# A607B.net
KiCad netlist of a schematic drawn in EAGLE
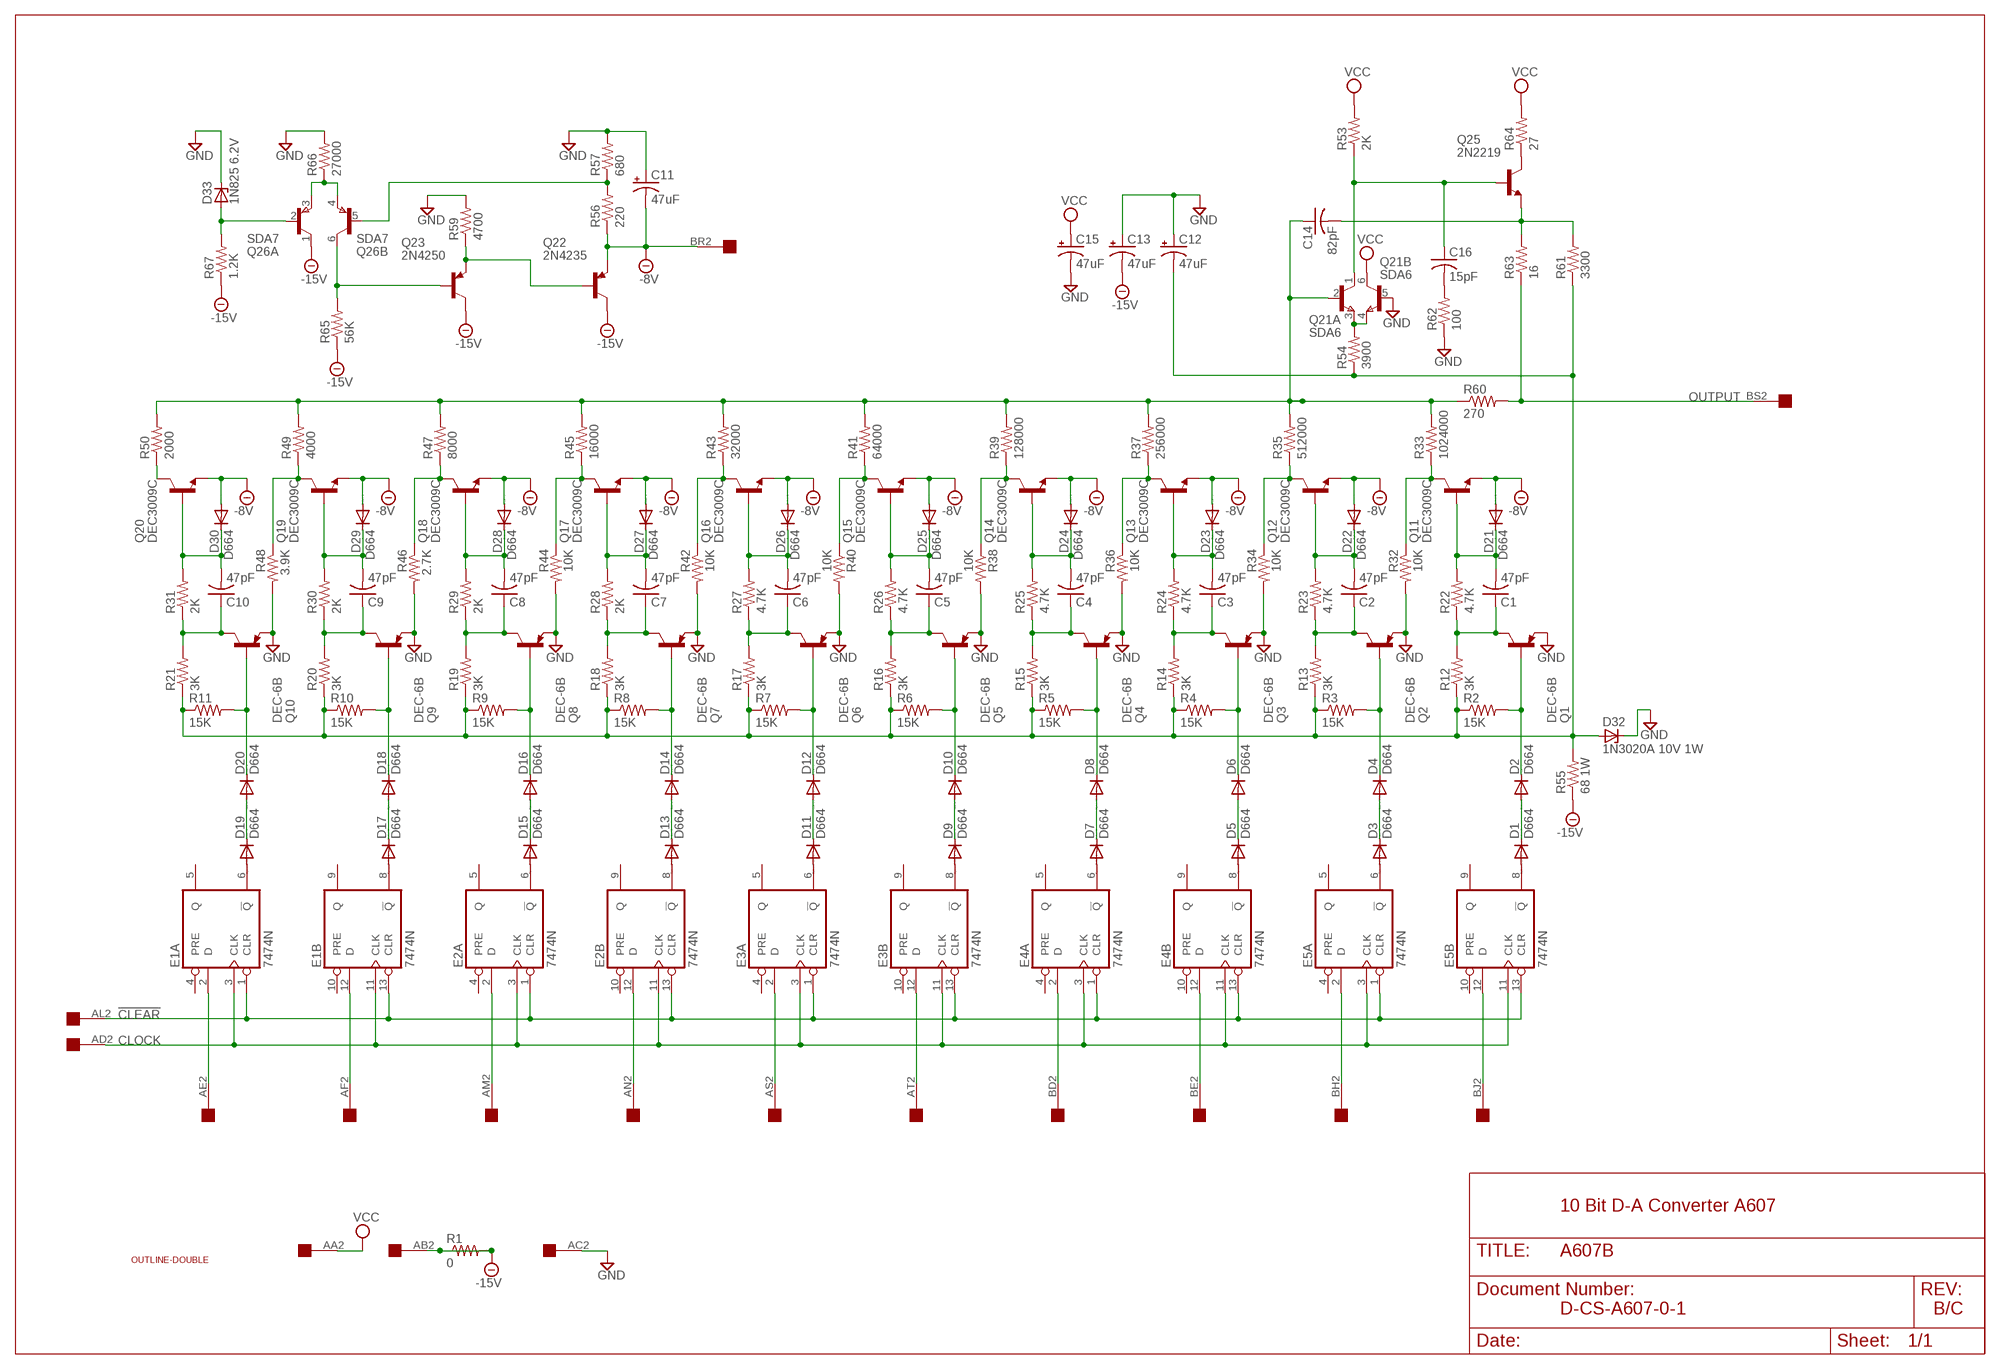
[diagram p0: schematic, sheet 1]

(export (version "E")
  (design (tool "Eeschema 10.0.6"))
  (components
    (comp (ref "C1")
      (value "47pF")
      (footprint "eagle-import:C075-032X103")
      (libsource (lib "eagle-import") (part "C-US075-032X103"))
    )
    (comp (ref "C2")
      (value "47pF")
      (footprint "eagle-import:C075-032X103")
      (libsource (lib "eagle-import") (part "C-US075-032X103"))
    )
    (comp (ref "C3")
      (value "47pF")
      (footprint "eagle-import:C075-032X103")
      (libsource (lib "eagle-import") (part "C-US075-032X103"))
    )
    (comp (ref "C4")
      (value "47pF")
      (footprint "eagle-import:C075-032X103")
      (libsource (lib "eagle-import") (part "C-US075-032X103"))
    )
    (comp (ref "C5")
      (value "47pF")
      (footprint "eagle-import:C075-032X103")
      (libsource (lib "eagle-import") (part "C-US075-032X103"))
    )
    (comp (ref "C6")
      (value "47pF")
      (footprint "eagle-import:C075-032X103")
      (libsource (lib "eagle-import") (part "C-US075-032X103"))
    )
    (comp (ref "C7")
      (value "47pF")
      (footprint "eagle-import:C075-032X103")
      (libsource (lib "eagle-import") (part "C-US075-032X103"))
    )
    (comp (ref "C8")
      (value "47pF")
      (footprint "eagle-import:C075-032X103")
      (libsource (lib "eagle-import") (part "C-US075-032X103"))
    )
    (comp (ref "C9")
      (value "47pF")
      (footprint "eagle-import:C075-032X103")
      (libsource (lib "eagle-import") (part "C-US075-032X103"))
    )
    (comp (ref "C10")
      (value "47pF")
      (footprint "eagle-import:C075-032X103")
      (libsource (lib "eagle-import") (part "C-US075-032X103"))
    )
    (comp (ref "C11")
      (value "47uF")
      (footprint "eagle-import:E25-9")
      (libsource (lib "eagle-import") (part "CPOL-USE25-9AXIAL"))
    )
    (comp (ref "C12")
      (value "47uF")
      (footprint "eagle-import:E25-9")
      (libsource (lib "eagle-import") (part "CPOL-USE25-9AXIAL"))
    )
    (comp (ref "C13")
      (value "47uF")
      (footprint "eagle-import:E25-9")
      (libsource (lib "eagle-import") (part "CPOL-USE25-9AXIAL"))
    )
    (comp (ref "C14")
      (value "82pF")
      (footprint "eagle-import:C050-025X075")
      (libsource (lib "eagle-import") (part "C-US050-025X075"))
    )
    (comp (ref "C15")
      (value "47uF")
      (footprint "eagle-import:E25-9")
      (libsource (lib "eagle-import") (part "CPOL-USE25-9AXIAL"))
    )
    (comp (ref "C16")
      (value "15pF")
      (footprint "eagle-import:C050-025X075")
      (libsource (lib "eagle-import") (part "C-US050-025X075"))
    )
    (comp (ref "D1")
      (value "D664")
      (footprint "eagle-import:DO35-10")
      (libsource (lib "eagle-import") (part "DIODE-DO35-10"))
    )
    (comp (ref "D2")
      (value "D664")
      (footprint "eagle-import:DO35-10")
      (libsource (lib "eagle-import") (part "DIODE-DO35-10"))
    )
    (comp (ref "D3")
      (value "D664")
      (footprint "eagle-import:DO35-10")
      (libsource (lib "eagle-import") (part "DIODE-DO35-10"))
    )
    (comp (ref "D4")
      (value "D664")
      (footprint "eagle-import:DO35-10")
      (libsource (lib "eagle-import") (part "DIODE-DO35-10"))
    )
    (comp (ref "D5")
      (value "D664")
      (footprint "eagle-import:DO35-10")
      (libsource (lib "eagle-import") (part "DIODE-DO35-10"))
    )
    (comp (ref "D6")
      (value "D664")
      (footprint "eagle-import:DO35-10")
      (libsource (lib "eagle-import") (part "DIODE-DO35-10"))
    )
    (comp (ref "D7")
      (value "D664")
      (footprint "eagle-import:DO35-10")
      (libsource (lib "eagle-import") (part "DIODE-DO35-10"))
    )
    (comp (ref "D8")
      (value "D664")
      (footprint "eagle-import:DO35-10")
      (libsource (lib "eagle-import") (part "DIODE-DO35-10"))
    )
    (comp (ref "D9")
      (value "D664")
      (footprint "eagle-import:DO35-10")
      (libsource (lib "eagle-import") (part "DIODE-DO35-10"))
    )
    (comp (ref "D10")
      (value "D664")
      (footprint "eagle-import:DO35-10")
      (libsource (lib "eagle-import") (part "DIODE-DO35-10"))
    )
    (comp (ref "D11")
      (value "D664")
      (footprint "eagle-import:DO35-10")
      (libsource (lib "eagle-import") (part "DIODE-DO35-10"))
    )
    (comp (ref "D12")
      (value "D664")
      (footprint "eagle-import:DO35-10")
      (libsource (lib "eagle-import") (part "DIODE-DO35-10"))
    )
    (comp (ref "D13")
      (value "D664")
      (footprint "eagle-import:DO35-10")
      (libsource (lib "eagle-import") (part "DIODE-DO35-10"))
    )
    (comp (ref "D14")
      (value "D664")
      (footprint "eagle-import:DO35-10")
      (libsource (lib "eagle-import") (part "DIODE-DO35-10"))
    )
    (comp (ref "D15")
      (value "D664")
      (footprint "eagle-import:DO35-10")
      (libsource (lib "eagle-import") (part "DIODE-DO35-10"))
    )
    (comp (ref "D16")
      (value "D664")
      (footprint "eagle-import:DO35-10")
      (libsource (lib "eagle-import") (part "DIODE-DO35-10"))
    )
    (comp (ref "D17")
      (value "D664")
      (footprint "eagle-import:DO35-10")
      (libsource (lib "eagle-import") (part "DIODE-DO35-10"))
    )
    (comp (ref "D18")
      (value "D664")
      (footprint "eagle-import:DO35-10")
      (libsource (lib "eagle-import") (part "DIODE-DO35-10"))
    )
    (comp (ref "D19")
      (value "D664")
      (footprint "eagle-import:DO35-10")
      (libsource (lib "eagle-import") (part "DIODE-DO35-10"))
    )
    (comp (ref "D20")
      (value "D664")
      (footprint "eagle-import:DO35-10")
      (libsource (lib "eagle-import") (part "DIODE-DO35-10"))
    )
    (comp (ref "D21")
      (value "D664")
      (footprint "eagle-import:DO35-10")
      (libsource (lib "eagle-import") (part "DIODE-DO35-10"))
    )
    (comp (ref "D22")
      (value "D664")
      (footprint "eagle-import:DO35-10")
      (libsource (lib "eagle-import") (part "DIODE-DO35-10"))
    )
    (comp (ref "D23")
      (value "D664")
      (footprint "eagle-import:DO35-10")
      (libsource (lib "eagle-import") (part "DIODE-DO35-10"))
    )
    (comp (ref "D24")
      (value "D664")
      (footprint "eagle-import:DO35-10")
      (libsource (lib "eagle-import") (part "DIODE-DO35-10"))
    )
    (comp (ref "D25")
      (value "D664")
      (footprint "eagle-import:DO35-10")
      (libsource (lib "eagle-import") (part "DIODE-DO35-10"))
    )
    (comp (ref "D26")
      (value "D664")
      (footprint "eagle-import:DO35-10")
      (libsource (lib "eagle-import") (part "DIODE-DO35-10"))
    )
    (comp (ref "D27")
      (value "D664")
      (footprint "eagle-import:DO35-10")
      (libsource (lib "eagle-import") (part "DIODE-DO35-10"))
    )
    (comp (ref "D28")
      (value "D664")
      (footprint "eagle-import:DO35-10")
      (libsource (lib "eagle-import") (part "DIODE-DO35-10"))
    )
    (comp (ref "D29")
      (value "D664")
      (footprint "eagle-import:DO35-10")
      (libsource (lib "eagle-import") (part "DIODE-DO35-10"))
    )
    (comp (ref "D30")
      (value "D664")
      (footprint "eagle-import:DO35-10")
      (libsource (lib "eagle-import") (part "DIODE-DO35-10"))
    )
    (comp (ref "D32")
      (value "1N3020A 10V 1W")
      (footprint "eagle-import:DO13M")
      (libsource (lib "eagle-import") (part "ZENER-DIODEDO13M"))
    )
    (comp (ref "D33")
      (value "1N825 6.2V")
      (footprint "eagle-import:DO35Z10")
      (libsource (lib "eagle-import") (part "ZENER-DIODEDO35Z10"))
    )
    (comp (ref "E1")
      (value "7474N")
      (footprint "eagle-import:DIL14")
      (libsource (lib "eagle-import") (part "7474NS"))
    )
    (comp (ref "E2")
      (value "7474N")
      (footprint "eagle-import:DIL14")
      (libsource (lib "eagle-import") (part "7474NS"))
    )
    (comp (ref "E3")
      (value "7474N")
      (footprint "eagle-import:DIL14")
      (libsource (lib "eagle-import") (part "7474NS"))
    )
    (comp (ref "E4")
      (value "7474N")
      (footprint "eagle-import:DIL14")
      (libsource (lib "eagle-import") (part "7474NS"))
    )
    (comp (ref "E5")
      (value "7474N")
      (footprint "eagle-import:DIL14")
      (libsource (lib "eagle-import") (part "7474NS"))
    )
    (comp (ref "Q1")
      (value "DEC-6B")
      (footprint "eagle-import:TO5")
      (libsource (lib "eagle-import") (part "-PNP-TO5"))
    )
    (comp (ref "Q2")
      (value "DEC-6B")
      (footprint "eagle-import:TO5")
      (libsource (lib "eagle-import") (part "-PNP-TO5"))
    )
    (comp (ref "Q3")
      (value "DEC-6B")
      (footprint "eagle-import:TO5")
      (libsource (lib "eagle-import") (part "-PNP-TO5"))
    )
    (comp (ref "Q4")
      (value "DEC-6B")
      (footprint "eagle-import:TO5")
      (libsource (lib "eagle-import") (part "-PNP-TO5"))
    )
    (comp (ref "Q5")
      (value "DEC-6B")
      (footprint "eagle-import:TO5")
      (libsource (lib "eagle-import") (part "-PNP-TO5"))
    )
    (comp (ref "Q6")
      (value "DEC-6B")
      (footprint "eagle-import:TO5")
      (libsource (lib "eagle-import") (part "-PNP-TO5"))
    )
    (comp (ref "Q7")
      (value "DEC-6B")
      (footprint "eagle-import:TO5")
      (libsource (lib "eagle-import") (part "-PNP-TO5"))
    )
    (comp (ref "Q8")
      (value "DEC-6B")
      (footprint "eagle-import:TO5")
      (libsource (lib "eagle-import") (part "-PNP-TO5"))
    )
    (comp (ref "Q9")
      (value "DEC-6B")
      (footprint "eagle-import:TO5")
      (libsource (lib "eagle-import") (part "-PNP-TO5"))
    )
    (comp (ref "Q10")
      (value "DEC-6B")
      (footprint "eagle-import:TO5")
      (libsource (lib "eagle-import") (part "-PNP-TO5"))
    )
    (comp (ref "Q11")
      (value "DEC3009C")
      (footprint "eagle-import:TO5")
      (libsource (lib "eagle-import") (part "-NPN-TO5"))
    )
    (comp (ref "Q12")
      (value "DEC3009C")
      (footprint "eagle-import:TO5")
      (libsource (lib "eagle-import") (part "-NPN-TO5"))
    )
    (comp (ref "Q13")
      (value "DEC3009C")
      (footprint "eagle-import:TO5")
      (libsource (lib "eagle-import") (part "-NPN-TO5"))
    )
    (comp (ref "Q14")
      (value "DEC3009C")
      (footprint "eagle-import:TO5")
      (libsource (lib "eagle-import") (part "-NPN-TO5"))
    )
    (comp (ref "Q15")
      (value "DEC3009C")
      (footprint "eagle-import:TO5")
      (libsource (lib "eagle-import") (part "-NPN-TO5"))
    )
    (comp (ref "Q16")
      (value "DEC3009C")
      (footprint "eagle-import:TO5")
      (libsource (lib "eagle-import") (part "-NPN-TO5"))
    )
    (comp (ref "Q17")
      (value "DEC3009C")
      (footprint "eagle-import:TO5")
      (libsource (lib "eagle-import") (part "-NPN-TO5"))
    )
    (comp (ref "Q18")
      (value "DEC3009C")
      (footprint "eagle-import:TO5")
      (libsource (lib "eagle-import") (part "-NPN-TO5"))
    )
    (comp (ref "Q19")
      (value "DEC3009C")
      (footprint "eagle-import:TO5")
      (libsource (lib "eagle-import") (part "-NPN-TO5"))
    )
    (comp (ref "Q20")
      (value "DEC3009C")
      (footprint "eagle-import:TO5")
      (libsource (lib "eagle-import") (part "-NPN-TO5"))
    )
    (comp (ref "Q21")
      (value "SDA6")
      (footprint "eagle-import:TO78")
      (libsource (lib "eagle-import") (part "MAT-02H"))
    )
    (comp (ref "Q22")
      (value "2N4235")
      (footprint "eagle-import:TO5")
      (libsource (lib "eagle-import") (part "-PNP-TO5"))
    )
    (comp (ref "Q23")
      (value "2N4250")
      (footprint "eagle-import:TO5")
      (libsource (lib "eagle-import") (part "-PNP-TO5"))
    )
    (comp (ref "Q25")
      (value "2N2219")
      (footprint "eagle-import:TO5")
      (libsource (lib "eagle-import") (part "-NPN-TO5"))
    )
    (comp (ref "Q26")
      (value "SDA7")
      (footprint "eagle-import:TO78")
      (libsource (lib "eagle-import") (part "MAT-03H"))
    )
    (comp (ref "R1")
      (value "0")
      (footprint "eagle-import:0818_25")
      (libsource (lib "eagle-import") (part "R-US_0818/25"))
    )
    (comp (ref "R2")
      (value "15K")
      (footprint "eagle-import:0207_10")
      (libsource (lib "eagle-import") (part "R-US_0207/10"))
    )
    (comp (ref "R3")
      (value "15K")
      (footprint "eagle-import:0207_10")
      (libsource (lib "eagle-import") (part "R-US_0207/10"))
    )
    (comp (ref "R4")
      (value "15K")
      (footprint "eagle-import:0207_10")
      (libsource (lib "eagle-import") (part "R-US_0207/10"))
    )
    (comp (ref "R5")
      (value "15K")
      (footprint "eagle-import:0207_10")
      (libsource (lib "eagle-import") (part "R-US_0207/10"))
    )
    (comp (ref "R6")
      (value "15K")
      (footprint "eagle-import:0207_10")
      (libsource (lib "eagle-import") (part "R-US_0207/10"))
    )
    (comp (ref "R7")
      (value "15K")
      (footprint "eagle-import:0207_10")
      (libsource (lib "eagle-import") (part "R-US_0207/10"))
    )
    (comp (ref "R8")
      (value "15K")
      (footprint "eagle-import:0207_10")
      (libsource (lib "eagle-import") (part "R-US_0207/10"))
    )
    (comp (ref "R9")
      (value "15K")
      (footprint "eagle-import:0207_10")
      (libsource (lib "eagle-import") (part "R-US_0207/10"))
    )
    (comp (ref "R10")
      (value "15K")
      (footprint "eagle-import:0207_10")
      (libsource (lib "eagle-import") (part "R-US_0207/10"))
    )
    (comp (ref "R11")
      (value "15K")
      (footprint "eagle-import:0207_10")
      (libsource (lib "eagle-import") (part "R-US_0207/10"))
    )
    (comp (ref "R12")
      (value "3K")
      (footprint "eagle-import:0207_10")
      (libsource (lib "eagle-import") (part "R-US_0207/10"))
    )
    (comp (ref "R13")
      (value "3K")
      (footprint "eagle-import:0207_10")
      (libsource (lib "eagle-import") (part "R-US_0207/10"))
    )
    (comp (ref "R14")
      (value "3K")
      (footprint "eagle-import:0207_10")
      (libsource (lib "eagle-import") (part "R-US_0207/10"))
    )
    (comp (ref "R15")
      (value "3K")
      (footprint "eagle-import:0207_10")
      (libsource (lib "eagle-import") (part "R-US_0207/10"))
    )
    (comp (ref "R16")
      (value "3K")
      (footprint "eagle-import:0207_10")
      (libsource (lib "eagle-import") (part "R-US_0207/10"))
    )
    (comp (ref "R17")
      (value "3K")
      (footprint "eagle-import:0207_10")
      (libsource (lib "eagle-import") (part "R-US_0207/10"))
    )
    (comp (ref "R18")
      (value "3K")
      (footprint "eagle-import:0207_10")
      (libsource (lib "eagle-import") (part "R-US_0207/10"))
    )
    (comp (ref "R19")
      (value "3K")
      (footprint "eagle-import:0207_10")
      (libsource (lib "eagle-import") (part "R-US_0207/10"))
    )
    (comp (ref "R20")
      (value "3K")
      (footprint "eagle-import:0207_10")
      (libsource (lib "eagle-import") (part "R-US_0207/10"))
    )
    (comp (ref "R21")
      (value "3K")
      (footprint "eagle-import:0207_10")
      (libsource (lib "eagle-import") (part "R-US_0207/10"))
    )
    (comp (ref "R22")
      (value "4.7K")
      (footprint "eagle-import:0207_10")
      (libsource (lib "eagle-import") (part "R-US_0207/10"))
    )
    (comp (ref "R23")
      (value "4.7K")
      (footprint "eagle-import:0207_10")
      (libsource (lib "eagle-import") (part "R-US_0207/10"))
    )
    (comp (ref "R24")
      (value "4.7K")
      (footprint "eagle-import:0207_10")
      (libsource (lib "eagle-import") (part "R-US_0207/10"))
    )
    (comp (ref "R25")
      (value "4.7K")
      (footprint "eagle-import:0207_10")
      (libsource (lib "eagle-import") (part "R-US_0207/10"))
    )
    (comp (ref "R26")
      (value "4.7K")
      (footprint "eagle-import:0207_10")
      (libsource (lib "eagle-import") (part "R-US_0207/10"))
    )
    (comp (ref "R27")
      (value "4.7K")
      (footprint "eagle-import:0207_10")
      (libsource (lib "eagle-import") (part "R-US_0207/10"))
    )
    (comp (ref "R28")
      (value "2K")
      (footprint "eagle-import:0207_10")
      (libsource (lib "eagle-import") (part "R-US_0207/10"))
    )
    (comp (ref "R29")
      (value "2K")
      (footprint "eagle-import:0207_10")
      (libsource (lib "eagle-import") (part "R-US_0207/10"))
    )
    (comp (ref "R30")
      (value "2K")
      (footprint "eagle-import:0207_10")
      (libsource (lib "eagle-import") (part "R-US_0207/10"))
    )
    (comp (ref "R31")
      (value "2K")
      (footprint "eagle-import:0207_10")
      (libsource (lib "eagle-import") (part "R-US_0207/10"))
    )
    (comp (ref "R32")
      (value "10K")
      (footprint "eagle-import:0207_10")
      (libsource (lib "eagle-import") (part "R-US_0207/10"))
    )
    (comp (ref "R33")
      (value "1024000")
      (footprint "eagle-import:0414_20")
      (libsource (lib "eagle-import") (part "R-US_0414/20"))
    )
    (comp (ref "R34")
      (value "10K")
      (footprint "eagle-import:0207_10")
      (libsource (lib "eagle-import") (part "R-US_0207/10"))
    )
    (comp (ref "R35")
      (value "512000")
      (footprint "eagle-import:0414_20")
      (libsource (lib "eagle-import") (part "R-US_0414/20"))
    )
    (comp (ref "R36")
      (value "10K")
      (footprint "eagle-import:0207_10")
      (libsource (lib "eagle-import") (part "R-US_0207/10"))
    )
    (comp (ref "R37")
      (value "256000")
      (footprint "eagle-import:0207_15")
      (libsource (lib "eagle-import") (part "R-US_0207/15"))
    )
    (comp (ref "R38")
      (value "10K")
      (footprint "eagle-import:0207_10")
      (libsource (lib "eagle-import") (part "R-US_0207/10"))
    )
    (comp (ref "R39")
      (value "128000")
      (footprint "eagle-import:0207_15")
      (libsource (lib "eagle-import") (part "R-US_0207/15"))
    )
    (comp (ref "R40")
      (value "10K")
      (footprint "eagle-import:0207_10")
      (libsource (lib "eagle-import") (part "R-US_0207/10"))
    )
    (comp (ref "R41")
      (value "64000")
      (footprint "eagle-import:0207_15")
      (libsource (lib "eagle-import") (part "R-US_0207/15"))
    )
    (comp (ref "R42")
      (value "10K")
      (footprint "eagle-import:0207_10")
      (libsource (lib "eagle-import") (part "R-US_0207/10"))
    )
    (comp (ref "R43")
      (value "32000")
      (footprint "eagle-import:0207_15")
      (libsource (lib "eagle-import") (part "R-US_0207/15"))
    )
    (comp (ref "R44")
      (value "10K")
      (footprint "eagle-import:0207_10")
      (libsource (lib "eagle-import") (part "R-US_0207/10"))
    )
    (comp (ref "R45")
      (value "16000")
      (footprint "eagle-import:0207_15")
      (libsource (lib "eagle-import") (part "R-US_0207/15"))
    )
    (comp (ref "R46")
      (value "2.7K")
      (footprint "eagle-import:0207_10")
      (libsource (lib "eagle-import") (part "R-US_0207/10"))
    )
    (comp (ref "R47")
      (value "8000")
      (footprint "eagle-import:0207_15")
      (libsource (lib "eagle-import") (part "R-US_0207/15"))
    )
    (comp (ref "R48")
      (value "3.9K")
      (footprint "eagle-import:0207_10")
      (libsource (lib "eagle-import") (part "R-US_0207/10"))
    )
    (comp (ref "R49")
      (value "4000")
      (footprint "eagle-import:0207_15")
      (libsource (lib "eagle-import") (part "R-US_0207/15"))
    )
    (comp (ref "R50")
      (value "2000")
      (footprint "eagle-import:0207_15")
      (libsource (lib "eagle-import") (part "R-US_0207/15"))
    )
    (comp (ref "R53")
      (value "2K")
      (footprint "eagle-import:0207_10")
      (libsource (lib "eagle-import") (part "R-US_0207/10"))
    )
    (comp (ref "R54")
      (value "3900")
      (footprint "eagle-import:0207_10")
      (libsource (lib "eagle-import") (part "R-US_0207/10"))
    )
    (comp (ref "R55")
      (value "68 1W")
      (footprint "eagle-import:0818_25")
      (libsource (lib "eagle-import") (part "R-US_0818/25"))
    )
    (comp (ref "R56")
      (value "220")
      (footprint "eagle-import:0207_10")
      (libsource (lib "eagle-import") (part "R-US_0207/10"))
    )
    (comp (ref "R57")
      (value "680")
      (footprint "eagle-import:0207_10")
      (libsource (lib "eagle-import") (part "R-US_0207/10"))
    )
    (comp (ref "R59")
      (value "4700")
      (footprint "eagle-import:0207_10")
      (libsource (lib "eagle-import") (part "R-US_0207/10"))
    )
    (comp (ref "R60")
      (value "270")
      (footprint "eagle-import:0207_10")
      (libsource (lib "eagle-import") (part "R-US_0207/10"))
    )
    (comp (ref "R61")
      (value "3300")
      (footprint "eagle-import:0207_10")
      (libsource (lib "eagle-import") (part "R-US_0207/10"))
    )
    (comp (ref "R62")
      (value "100")
      (footprint "eagle-import:0207_10")
      (libsource (lib "eagle-import") (part "R-US_0207/10"))
    )
    (comp (ref "R63")
      (value "16")
      (footprint "eagle-import:0207_10")
      (libsource (lib "eagle-import") (part "R-US_0207/10"))
    )
    (comp (ref "R64")
      (value "27")
      (footprint "eagle-import:0207_10")
      (libsource (lib "eagle-import") (part "R-US_0207/10"))
    )
    (comp (ref "R65")
      (value "56K")
      (footprint "eagle-import:0207_10")
      (libsource (lib "eagle-import") (part "R-US_0207/10"))
    )
    (comp (ref "R66")
      (value "27000")
      (footprint "eagle-import:0207_10")
      (libsource (lib "eagle-import") (part "R-US_0207/10"))
    )
    (comp (ref "R67")
      (value "1.2K")
      (footprint "eagle-import:0207_10")
      (libsource (lib "eagle-import") (part "R-US_0207/10"))
    )
    (comp (ref "U$1")
      (value "OUTLINE-DOUBLE")
      (footprint "eagle-import:DOUBLE")
      (libsource (lib "eagle-import") (part "OUTLINE-DOUBLE"))
    )
    (comp (ref "U$2")
      (value "DOUBLE")
      (footprint "eagle-import:EDGE-CON4")
      (libsource (lib "eagle-import") (part "DOUBLE"))
    )
  )
  (nets
    (net (code "1") (name "-8V") (class "Default")
      (node (ref "C11") (pin "-") (pinfunction "-_-") (pintype "passive"))
      (node (ref "D21") (pin "A") (pinfunction "A_A") (pintype "passive"))
      (node (ref "D22") (pin "A") (pinfunction "A_A") (pintype "passive"))
      (node (ref "D23") (pin "A") (pinfunction "A_A") (pintype "passive"))
      (node (ref "D24") (pin "A") (pinfunction "A_A") (pintype "passive"))
      (node (ref "D25") (pin "A") (pinfunction "A_A") (pintype "passive"))
      (node (ref "D26") (pin "A") (pinfunction "A_A") (pintype "passive"))
      (node (ref "D27") (pin "A") (pinfunction "A_A") (pintype "passive"))
      (node (ref "D28") (pin "A") (pinfunction "A_A") (pintype "passive"))
      (node (ref "D29") (pin "A") (pinfunction "A_A") (pintype "passive"))
      (node (ref "D30") (pin "A") (pinfunction "A_A") (pintype "passive"))
      (node (ref "Q11") (pin "1") (pinfunction "E_1") (pintype "passive"))
      (node (ref "Q12") (pin "1") (pinfunction "E_1") (pintype "passive"))
      (node (ref "Q13") (pin "1") (pinfunction "E_1") (pintype "passive"))
      (node (ref "Q14") (pin "1") (pinfunction "E_1") (pintype "passive"))
      (node (ref "Q15") (pin "1") (pinfunction "E_1") (pintype "passive"))
      (node (ref "Q16") (pin "1") (pinfunction "E_1") (pintype "passive"))
      (node (ref "Q17") (pin "1") (pinfunction "E_1") (pintype "passive"))
      (node (ref "Q18") (pin "1") (pinfunction "E_1") (pintype "passive"))
      (node (ref "Q19") (pin "1") (pinfunction "E_1") (pintype "passive"))
      (node (ref "Q20") (pin "1") (pinfunction "E_1") (pintype "passive"))
      (node (ref "Q22") (pin "1") (pinfunction "E_1") (pintype "passive"))
      (node (ref "R56") (pin "1") (pinfunction "1_1") (pintype "passive"))
      (node (ref "U$2") (pin "BR2") (pinfunction "1_BR2") (pintype "bidirectional"))
    )
    (net (code "2") (name "-15V") (class "Default")
      (node (ref "C13") (pin "-") (pinfunction "-_-") (pintype "passive"))
      (node (ref "Q22") (pin "3") (pinfunction "C_3") (pintype "passive"))
      (node (ref "Q23") (pin "3") (pinfunction "C_3") (pintype "passive"))
      (node (ref "Q26") (pin "1") (pinfunction "C_1") (pintype "passive"))
      (node (ref "R1") (pin "1") (pinfunction "1_1") (pintype "passive"))
      (node (ref "R1") (pin "2") (pinfunction "2_2") (pintype "passive"))
      (node (ref "R55") (pin "1") (pinfunction "1_1") (pintype "passive"))
      (node (ref "R65") (pin "1") (pinfunction "1_1") (pintype "passive"))
      (node (ref "R67") (pin "1") (pinfunction "1_1") (pintype "passive"))
      (node (ref "U$2") (pin "AB2") (pinfunction "1_AB2") (pintype "bidirectional"))
    )
    (net (code "3") (name "/CLOCK") (class "Default")
      (node (ref "E1") (pin "11") (pinfunction "CLK_11") (pintype "input"))
      (node (ref "E1") (pin "3") (pinfunction "CLK_3") (pintype "input"))
      (node (ref "E2") (pin "11") (pinfunction "CLK_11") (pintype "input"))
      (node (ref "E2") (pin "3") (pinfunction "CLK_3") (pintype "input"))
      (node (ref "E3") (pin "11") (pinfunction "CLK_11") (pintype "input"))
      (node (ref "E3") (pin "3") (pinfunction "CLK_3") (pintype "input"))
      (node (ref "E4") (pin "11") (pinfunction "CLK_11") (pintype "input"))
      (node (ref "E4") (pin "3") (pinfunction "CLK_3") (pintype "input"))
      (node (ref "E5") (pin "11") (pinfunction "CLK_11") (pintype "input"))
      (node (ref "E5") (pin "3") (pinfunction "CLK_3") (pintype "input"))
      (node (ref "U$2") (pin "AD2") (pinfunction "1_AD2") (pintype "bidirectional"))
    )
    (net (code "4") (name "/OUTPUT") (class "Default")
      (node (ref "R60") (pin "2") (pinfunction "2_2") (pintype "passive"))
      (node (ref "R63") (pin "1") (pinfunction "1_1") (pintype "passive"))
      (node (ref "U$2") (pin "BS2") (pinfunction "1_BS2") (pintype "bidirectional"))
    )
    (net (code "5") (name "/~{CLEAR}") (class "Default")
      (node (ref "E1") (pin "1") (pinfunction "CLR_1") (pintype "input"))
      (node (ref "E1") (pin "13") (pinfunction "CLR_13") (pintype "input"))
      (node (ref "E2") (pin "1") (pinfunction "CLR_1") (pintype "input"))
      (node (ref "E2") (pin "13") (pinfunction "CLR_13") (pintype "input"))
      (node (ref "E3") (pin "1") (pinfunction "CLR_1") (pintype "input"))
      (node (ref "E3") (pin "13") (pinfunction "CLR_13") (pintype "input"))
      (node (ref "E4") (pin "1") (pinfunction "CLR_1") (pintype "input"))
      (node (ref "E4") (pin "13") (pinfunction "CLR_13") (pintype "input"))
      (node (ref "E5") (pin "1") (pinfunction "CLR_1") (pintype "input"))
      (node (ref "E5") (pin "13") (pinfunction "CLR_13") (pintype "input"))
      (node (ref "U$2") (pin "AL2") (pinfunction "1_AL2") (pintype "bidirectional"))
    )
    (net (code "6") (name "GND") (class "Default")
      (node (ref "C11") (pin "+") (pinfunction "+_+") (pintype "passive"))
      (node (ref "C12") (pin "+") (pinfunction "+_+") (pintype "passive"))
      (node (ref "C13") (pin "+") (pinfunction "+_+") (pintype "passive"))
      (node (ref "C15") (pin "-") (pinfunction "-_-") (pintype "passive"))
      (node (ref "D32") (pin "C") (pinfunction "C_C") (pintype "passive"))
      (node (ref "D33") (pin "C") (pinfunction "C_C") (pintype "passive"))
      (node (ref "Q1") (pin "1") (pinfunction "E_1") (pintype "passive"))
      (node (ref "Q10") (pin "1") (pinfunction "E_1") (pintype "passive"))
      (node (ref "Q2") (pin "1") (pinfunction "E_1") (pintype "passive"))
      (node (ref "Q21") (pin "5") (pinfunction "B_5") (pintype "passive"))
      (node (ref "Q3") (pin "1") (pinfunction "E_1") (pintype "passive"))
      (node (ref "Q4") (pin "1") (pinfunction "E_1") (pintype "passive"))
      (node (ref "Q5") (pin "1") (pinfunction "E_1") (pintype "passive"))
      (node (ref "Q6") (pin "1") (pinfunction "E_1") (pintype "passive"))
      (node (ref "Q7") (pin "1") (pinfunction "E_1") (pintype "passive"))
      (node (ref "Q8") (pin "1") (pinfunction "E_1") (pintype "passive"))
      (node (ref "Q9") (pin "1") (pinfunction "E_1") (pintype "passive"))
      (node (ref "R32") (pin "2") (pinfunction "2_2") (pintype "passive"))
      (node (ref "R34") (pin "2") (pinfunction "2_2") (pintype "passive"))
      (node (ref "R36") (pin "2") (pinfunction "2_2") (pintype "passive"))
      (node (ref "R38") (pin "2") (pinfunction "2_2") (pintype "passive"))
      (node (ref "R40") (pin "2") (pinfunction "2_2") (pintype "passive"))
      (node (ref "R42") (pin "2") (pinfunction "2_2") (pintype "passive"))
      (node (ref "R44") (pin "2") (pinfunction "2_2") (pintype "passive"))
      (node (ref "R46") (pin "2") (pinfunction "2_2") (pintype "passive"))
      (node (ref "R48") (pin "2") (pinfunction "2_2") (pintype "passive"))
      (node (ref "R57") (pin "2") (pinfunction "2_2") (pintype "passive"))
      (node (ref "R59") (pin "2") (pinfunction "2_2") (pintype "passive"))
      (node (ref "R62") (pin "1") (pinfunction "1_1") (pintype "passive"))
      (node (ref "R66") (pin "2") (pinfunction "2_2") (pintype "passive"))
      (node (ref "U$2") (pin "AC2") (pinfunction "1_AC2") (pintype "bidirectional"))
    )
    (net (code "7") (name "Net-(C12-Pad-)") (class "Default")
      (node (ref "C12") (pin "-") (pinfunction "-_-") (pintype "passive"))
      (node (ref "D32") (pin "A") (pinfunction "A_A") (pintype "passive"))
      (node (ref "R10") (pin "1") (pinfunction "1_1") (pintype "passive"))
      (node (ref "R11") (pin "1") (pinfunction "1_1") (pintype "passive"))
      (node (ref "R12") (pin "1") (pinfunction "1_1") (pintype "passive"))
      (node (ref "R13") (pin "1") (pinfunction "1_1") (pintype "passive"))
      (node (ref "R14") (pin "1") (pinfunction "1_1") (pintype "passive"))
      (node (ref "R15") (pin "1") (pinfunction "1_1") (pintype "passive"))
      (node (ref "R16") (pin "1") (pinfunction "1_1") (pintype "passive"))
      (node (ref "R17") (pin "1") (pinfunction "1_1") (pintype "passive"))
      (node (ref "R18") (pin "1") (pinfunction "1_1") (pintype "passive"))
      (node (ref "R19") (pin "1") (pinfunction "1_1") (pintype "passive"))
      (node (ref "R2") (pin "1") (pinfunction "1_1") (pintype "passive"))
      (node (ref "R20") (pin "1") (pinfunction "1_1") (pintype "passive"))
      (node (ref "R21") (pin "1") (pinfunction "1_1") (pintype "passive"))
      (node (ref "R3") (pin "1") (pinfunction "1_1") (pintype "passive"))
      (node (ref "R4") (pin "1") (pinfunction "1_1") (pintype "passive"))
      (node (ref "R5") (pin "1") (pinfunction "1_1") (pintype "passive"))
      (node (ref "R54") (pin "1") (pinfunction "1_1") (pintype "passive"))
      (node (ref "R55") (pin "2") (pinfunction "2_2") (pintype "passive"))
      (node (ref "R6") (pin "1") (pinfunction "1_1") (pintype "passive"))
      (node (ref "R61") (pin "1") (pinfunction "1_1") (pintype "passive"))
      (node (ref "R7") (pin "1") (pinfunction "1_1") (pintype "passive"))
      (node (ref "R8") (pin "1") (pinfunction "1_1") (pintype "passive"))
      (node (ref "R9") (pin "1") (pinfunction "1_1") (pintype "passive"))
    )
    (net (code "8") (name "Net-(C16-Pad2)") (class "Default")
      (node (ref "C16") (pin "2") (pinfunction "2_2") (pintype "passive"))
      (node (ref "R62") (pin "2") (pinfunction "2_2") (pintype "passive"))
    )
    (net (code "9") (name "Net-(D1-PadC)") (class "Default")
      (node (ref "D1") (pin "C") (pinfunction "C_C") (pintype "passive"))
      (node (ref "D2") (pin "A") (pinfunction "A_A") (pintype "passive"))
    )
    (net (code "10") (name "Net-(D3-PadC)") (class "Default")
      (node (ref "D3") (pin "C") (pinfunction "C_C") (pintype "passive"))
      (node (ref "D4") (pin "A") (pinfunction "A_A") (pintype "passive"))
    )
    (net (code "11") (name "Net-(D5-PadC)") (class "Default")
      (node (ref "D5") (pin "C") (pinfunction "C_C") (pintype "passive"))
      (node (ref "D6") (pin "A") (pinfunction "A_A") (pintype "passive"))
    )
    (net (code "12") (name "Net-(D7-PadC)") (class "Default")
      (node (ref "D7") (pin "C") (pinfunction "C_C") (pintype "passive"))
      (node (ref "D8") (pin "A") (pinfunction "A_A") (pintype "passive"))
    )
    (net (code "13") (name "Net-(D10-PadA)") (class "Default")
      (node (ref "D10") (pin "A") (pinfunction "A_A") (pintype "passive"))
      (node (ref "D9") (pin "C") (pinfunction "C_C") (pintype "passive"))
    )
    (net (code "14") (name "Net-(D11-PadC)") (class "Default")
      (node (ref "D11") (pin "C") (pinfunction "C_C") (pintype "passive"))
      (node (ref "D12") (pin "A") (pinfunction "A_A") (pintype "passive"))
    )
    (net (code "15") (name "Net-(D13-PadC)") (class "Default")
      (node (ref "D13") (pin "C") (pinfunction "C_C") (pintype "passive"))
      (node (ref "D14") (pin "A") (pinfunction "A_A") (pintype "passive"))
    )
    (net (code "16") (name "Net-(D15-PadC)") (class "Default")
      (node (ref "D15") (pin "C") (pinfunction "C_C") (pintype "passive"))
      (node (ref "D16") (pin "A") (pinfunction "A_A") (pintype "passive"))
    )
    (net (code "17") (name "Net-(D17-PadC)") (class "Default")
      (node (ref "D17") (pin "C") (pinfunction "C_C") (pintype "passive"))
      (node (ref "D18") (pin "A") (pinfunction "A_A") (pintype "passive"))
    )
    (net (code "18") (name "Net-(D19-PadC)") (class "Default")
      (node (ref "D19") (pin "C") (pinfunction "C_C") (pintype "passive"))
      (node (ref "D20") (pin "A") (pinfunction "A_A") (pintype "passive"))
    )
    (net (code "19") (name "Net-(E1A-D)") (class "Default")
      (node (ref "E1") (pin "2") (pinfunction "D_2") (pintype "input"))
      (node (ref "U$2") (pin "AE2") (pinfunction "1_AE2") (pintype "bidirectional"))
    )
    (net (code "20") (name "Net-(E1A-~{Q})") (class "Default")
      (node (ref "D19") (pin "A") (pinfunction "A_A") (pintype "passive"))
      (node (ref "E1") (pin "6") (pinfunction "~{Q}_6") (pintype "output"))
    )
    (net (code "21") (name "Net-(E1B-D)") (class "Default")
      (node (ref "E1") (pin "12") (pinfunction "D_12") (pintype "input"))
      (node (ref "U$2") (pin "AF2") (pinfunction "1_AF2") (pintype "bidirectional"))
    )
    (net (code "22") (name "Net-(E1B-~{Q})") (class "Default")
      (node (ref "D17") (pin "A") (pinfunction "A_A") (pintype "passive"))
      (node (ref "E1") (pin "8") (pinfunction "~{Q}_8") (pintype "output"))
    )
    (net (code "23") (name "Net-(E2A-D)") (class "Default")
      (node (ref "E2") (pin "2") (pinfunction "D_2") (pintype "input"))
      (node (ref "U$2") (pin "AM2") (pinfunction "1_AM2") (pintype "bidirectional"))
    )
    (net (code "24") (name "Net-(E2A-~{Q})") (class "Default")
      (node (ref "D15") (pin "A") (pinfunction "A_A") (pintype "passive"))
      (node (ref "E2") (pin "6") (pinfunction "~{Q}_6") (pintype "output"))
    )
    (net (code "25") (name "Net-(E2B-D)") (class "Default")
      (node (ref "E2") (pin "12") (pinfunction "D_12") (pintype "input"))
      (node (ref "U$2") (pin "AN2") (pinfunction "1_AN2") (pintype "bidirectional"))
    )
    (net (code "26") (name "Net-(E2B-~{Q})") (class "Default")
      (node (ref "D13") (pin "A") (pinfunction "A_A") (pintype "passive"))
      (node (ref "E2") (pin "8") (pinfunction "~{Q}_8") (pintype "output"))
    )
    (net (code "27") (name "Net-(E3A-D)") (class "Default")
      (node (ref "E3") (pin "2") (pinfunction "D_2") (pintype "input"))
      (node (ref "U$2") (pin "AS2") (pinfunction "1_AS2") (pintype "bidirectional"))
    )
    (net (code "28") (name "Net-(E3A-~{Q})") (class "Default")
      (node (ref "D11") (pin "A") (pinfunction "A_A") (pintype "passive"))
      (node (ref "E3") (pin "6") (pinfunction "~{Q}_6") (pintype "output"))
    )
    (net (code "29") (name "Net-(E3B-D)") (class "Default")
      (node (ref "E3") (pin "12") (pinfunction "D_12") (pintype "input"))
      (node (ref "U$2") (pin "AT2") (pinfunction "1_AT2") (pintype "bidirectional"))
    )
    (net (code "30") (name "Net-(E3B-~{Q})") (class "Default")
      (node (ref "D9") (pin "A") (pinfunction "A_A") (pintype "passive"))
      (node (ref "E3") (pin "8") (pinfunction "~{Q}_8") (pintype "output"))
    )
    (net (code "31") (name "Net-(E4A-D)") (class "Default")
      (node (ref "E4") (pin "2") (pinfunction "D_2") (pintype "input"))
      (node (ref "U$2") (pin "BD2") (pinfunction "1_BD2") (pintype "bidirectional"))
    )
    (net (code "32") (name "Net-(E4A-~{Q})") (class "Default")
      (node (ref "D7") (pin "A") (pinfunction "A_A") (pintype "passive"))
      (node (ref "E4") (pin "6") (pinfunction "~{Q}_6") (pintype "output"))
    )
    (net (code "33") (name "Net-(E4B-D)") (class "Default")
      (node (ref "E4") (pin "12") (pinfunction "D_12") (pintype "input"))
      (node (ref "U$2") (pin "BE2") (pinfunction "1_BE2") (pintype "bidirectional"))
    )
    (net (code "34") (name "Net-(E4B-~{Q})") (class "Default")
      (node (ref "D5") (pin "A") (pinfunction "A_A") (pintype "passive"))
      (node (ref "E4") (pin "8") (pinfunction "~{Q}_8") (pintype "output"))
    )
    (net (code "35") (name "Net-(E5A-D)") (class "Default")
      (node (ref "E5") (pin "2") (pinfunction "D_2") (pintype "input"))
      (node (ref "U$2") (pin "BH2") (pinfunction "1_BH2") (pintype "bidirectional"))
    )
    (net (code "36") (name "Net-(E5A-~{Q})") (class "Default")
      (node (ref "D3") (pin "A") (pinfunction "A_A") (pintype "passive"))
      (node (ref "E5") (pin "6") (pinfunction "~{Q}_6") (pintype "output"))
    )
    (net (code "37") (name "Net-(E5B-D)") (class "Default")
      (node (ref "E5") (pin "12") (pinfunction "D_12") (pintype "input"))
      (node (ref "U$2") (pin "BJ2") (pinfunction "1_BJ2") (pintype "bidirectional"))
    )
    (net (code "38") (name "Net-(E5B-~{Q})") (class "Default")
      (node (ref "D1") (pin "A") (pinfunction "A_A") (pintype "passive"))
      (node (ref "E5") (pin "8") (pinfunction "~{Q}_8") (pintype "output"))
    )
    (net (code "39") (name "Net-(Q1-B)") (class "Default")
      (node (ref "D2") (pin "C") (pinfunction "C_C") (pintype "passive"))
      (node (ref "Q1") (pin "2") (pinfunction "B_2") (pintype "passive"))
      (node (ref "R2") (pin "2") (pinfunction "2_2") (pintype "passive"))
    )
    (net (code "40") (name "Net-(Q1-C)") (class "Default")
      (node (ref "C1") (pin "1") (pinfunction "1_1") (pintype "passive"))
      (node (ref "Q1") (pin "3") (pinfunction "C_3") (pintype "passive"))
      (node (ref "R12") (pin "2") (pinfunction "2_2") (pintype "passive"))
      (node (ref "R22") (pin "1") (pinfunction "1_1") (pintype "passive"))
    )
    (net (code "41") (name "Net-(Q2-B)") (class "Default")
      (node (ref "D4") (pin "C") (pinfunction "C_C") (pintype "passive"))
      (node (ref "Q2") (pin "2") (pinfunction "B_2") (pintype "passive"))
      (node (ref "R3") (pin "2") (pinfunction "2_2") (pintype "passive"))
    )
    (net (code "42") (name "Net-(Q2-C)") (class "Default")
      (node (ref "C2") (pin "1") (pinfunction "1_1") (pintype "passive"))
      (node (ref "Q2") (pin "3") (pinfunction "C_3") (pintype "passive"))
      (node (ref "R13") (pin "2") (pinfunction "2_2") (pintype "passive"))
      (node (ref "R23") (pin "1") (pinfunction "1_1") (pintype "passive"))
    )
    (net (code "43") (name "Net-(Q3-B)") (class "Default")
      (node (ref "D6") (pin "C") (pinfunction "C_C") (pintype "passive"))
      (node (ref "Q3") (pin "2") (pinfunction "B_2") (pintype "passive"))
      (node (ref "R4") (pin "2") (pinfunction "2_2") (pintype "passive"))
    )
    (net (code "44") (name "Net-(Q3-C)") (class "Default")
      (node (ref "C3") (pin "1") (pinfunction "1_1") (pintype "passive"))
      (node (ref "Q3") (pin "3") (pinfunction "C_3") (pintype "passive"))
      (node (ref "R14") (pin "2") (pinfunction "2_2") (pintype "passive"))
      (node (ref "R24") (pin "1") (pinfunction "1_1") (pintype "passive"))
    )
    (net (code "45") (name "Net-(Q4-B)") (class "Default")
      (node (ref "D8") (pin "C") (pinfunction "C_C") (pintype "passive"))
      (node (ref "Q4") (pin "2") (pinfunction "B_2") (pintype "passive"))
      (node (ref "R5") (pin "2") (pinfunction "2_2") (pintype "passive"))
    )
    (net (code "46") (name "Net-(Q4-C)") (class "Default")
      (node (ref "C4") (pin "1") (pinfunction "1_1") (pintype "passive"))
      (node (ref "Q4") (pin "3") (pinfunction "C_3") (pintype "passive"))
      (node (ref "R15") (pin "2") (pinfunction "2_2") (pintype "passive"))
      (node (ref "R25") (pin "1") (pinfunction "1_1") (pintype "passive"))
    )
    (net (code "47") (name "Net-(Q5-B)") (class "Default")
      (node (ref "D10") (pin "C") (pinfunction "C_C") (pintype "passive"))
      (node (ref "Q5") (pin "2") (pinfunction "B_2") (pintype "passive"))
      (node (ref "R6") (pin "2") (pinfunction "2_2") (pintype "passive"))
    )
    (net (code "48") (name "Net-(Q5-C)") (class "Default")
      (node (ref "C5") (pin "1") (pinfunction "1_1") (pintype "passive"))
      (node (ref "Q5") (pin "3") (pinfunction "C_3") (pintype "passive"))
      (node (ref "R16") (pin "2") (pinfunction "2_2") (pintype "passive"))
      (node (ref "R26") (pin "1") (pinfunction "1_1") (pintype "passive"))
    )
    (net (code "49") (name "Net-(Q6-B)") (class "Default")
      (node (ref "D12") (pin "C") (pinfunction "C_C") (pintype "passive"))
      (node (ref "Q6") (pin "2") (pinfunction "B_2") (pintype "passive"))
      (node (ref "R7") (pin "2") (pinfunction "2_2") (pintype "passive"))
    )
    (net (code "50") (name "Net-(Q6-C)") (class "Default")
      (node (ref "C6") (pin "1") (pinfunction "1_1") (pintype "passive"))
      (node (ref "Q6") (pin "3") (pinfunction "C_3") (pintype "passive"))
      (node (ref "R17") (pin "2") (pinfunction "2_2") (pintype "passive"))
      (node (ref "R27") (pin "1") (pinfunction "1_1") (pintype "passive"))
    )
    (net (code "51") (name "Net-(Q7-B)") (class "Default")
      (node (ref "D14") (pin "C") (pinfunction "C_C") (pintype "passive"))
      (node (ref "Q7") (pin "2") (pinfunction "B_2") (pintype "passive"))
      (node (ref "R8") (pin "2") (pinfunction "2_2") (pintype "passive"))
    )
    (net (code "52") (name "Net-(Q7-C)") (class "Default")
      (node (ref "C7") (pin "1") (pinfunction "1_1") (pintype "passive"))
      (node (ref "Q7") (pin "3") (pinfunction "C_3") (pintype "passive"))
      (node (ref "R18") (pin "2") (pinfunction "2_2") (pintype "passive"))
      (node (ref "R28") (pin "1") (pinfunction "1_1") (pintype "passive"))
    )
    (net (code "53") (name "Net-(Q8-B)") (class "Default")
      (node (ref "D16") (pin "C") (pinfunction "C_C") (pintype "passive"))
      (node (ref "Q8") (pin "2") (pinfunction "B_2") (pintype "passive"))
      (node (ref "R9") (pin "2") (pinfunction "2_2") (pintype "passive"))
    )
    (net (code "54") (name "Net-(Q8-C)") (class "Default")
      (node (ref "C8") (pin "1") (pinfunction "1_1") (pintype "passive"))
      (node (ref "Q8") (pin "3") (pinfunction "C_3") (pintype "passive"))
      (node (ref "R19") (pin "2") (pinfunction "2_2") (pintype "passive"))
      (node (ref "R29") (pin "1") (pinfunction "1_1") (pintype "passive"))
    )
    (net (code "55") (name "Net-(Q9-B)") (class "Default")
      (node (ref "D18") (pin "C") (pinfunction "C_C") (pintype "passive"))
      (node (ref "Q9") (pin "2") (pinfunction "B_2") (pintype "passive"))
      (node (ref "R10") (pin "2") (pinfunction "2_2") (pintype "passive"))
    )
    (net (code "56") (name "Net-(Q9-C)") (class "Default")
      (node (ref "C9") (pin "1") (pinfunction "1_1") (pintype "passive"))
      (node (ref "Q9") (pin "3") (pinfunction "C_3") (pintype "passive"))
      (node (ref "R20") (pin "2") (pinfunction "2_2") (pintype "passive"))
      (node (ref "R30") (pin "1") (pinfunction "1_1") (pintype "passive"))
    )
    (net (code "57") (name "Net-(Q10-B)") (class "Default")
      (node (ref "D20") (pin "C") (pinfunction "C_C") (pintype "passive"))
      (node (ref "Q10") (pin "2") (pinfunction "B_2") (pintype "passive"))
      (node (ref "R11") (pin "2") (pinfunction "2_2") (pintype "passive"))
    )
    (net (code "58") (name "Net-(Q10-C)") (class "Default")
      (node (ref "C10") (pin "1") (pinfunction "1_1") (pintype "passive"))
      (node (ref "Q10") (pin "3") (pinfunction "C_3") (pintype "passive"))
      (node (ref "R21") (pin "2") (pinfunction "2_2") (pintype "passive"))
      (node (ref "R31") (pin "1") (pinfunction "1_1") (pintype "passive"))
    )
    (net (code "59") (name "Net-(Q11-B)") (class "Default")
      (node (ref "C1") (pin "2") (pinfunction "2_2") (pintype "passive"))
      (node (ref "D21") (pin "C") (pinfunction "C_C") (pintype "passive"))
      (node (ref "Q11") (pin "2") (pinfunction "B_2") (pintype "passive"))
      (node (ref "R22") (pin "2") (pinfunction "2_2") (pintype "passive"))
    )
    (net (code "60") (name "Net-(Q11-C)") (class "Default")
      (node (ref "Q11") (pin "3") (pinfunction "C_3") (pintype "passive"))
      (node (ref "R32") (pin "1") (pinfunction "1_1") (pintype "passive"))
      (node (ref "R33") (pin "1") (pinfunction "1_1") (pintype "passive"))
    )
    (net (code "61") (name "Net-(Q12-B)") (class "Default")
      (node (ref "C2") (pin "2") (pinfunction "2_2") (pintype "passive"))
      (node (ref "D22") (pin "C") (pinfunction "C_C") (pintype "passive"))
      (node (ref "Q12") (pin "2") (pinfunction "B_2") (pintype "passive"))
      (node (ref "R23") (pin "2") (pinfunction "2_2") (pintype "passive"))
    )
    (net (code "62") (name "Net-(Q12-C)") (class "Default")
      (node (ref "Q12") (pin "3") (pinfunction "C_3") (pintype "passive"))
      (node (ref "R34") (pin "1") (pinfunction "1_1") (pintype "passive"))
      (node (ref "R35") (pin "1") (pinfunction "1_1") (pintype "passive"))
    )
    (net (code "63") (name "Net-(Q13-B)") (class "Default")
      (node (ref "C3") (pin "2") (pinfunction "2_2") (pintype "passive"))
      (node (ref "D23") (pin "C") (pinfunction "C_C") (pintype "passive"))
      (node (ref "Q13") (pin "2") (pinfunction "B_2") (pintype "passive"))
      (node (ref "R24") (pin "2") (pinfunction "2_2") (pintype "passive"))
    )
    (net (code "64") (name "Net-(Q13-C)") (class "Default")
      (node (ref "Q13") (pin "3") (pinfunction "C_3") (pintype "passive"))
      (node (ref "R36") (pin "1") (pinfunction "1_1") (pintype "passive"))
      (node (ref "R37") (pin "1") (pinfunction "1_1") (pintype "passive"))
    )
    (net (code "65") (name "Net-(Q14-B)") (class "Default")
      (node (ref "C4") (pin "2") (pinfunction "2_2") (pintype "passive"))
      (node (ref "D24") (pin "C") (pinfunction "C_C") (pintype "passive"))
      (node (ref "Q14") (pin "2") (pinfunction "B_2") (pintype "passive"))
      (node (ref "R25") (pin "2") (pinfunction "2_2") (pintype "passive"))
    )
    (net (code "66") (name "Net-(Q14-C)") (class "Default")
      (node (ref "Q14") (pin "3") (pinfunction "C_3") (pintype "passive"))
      (node (ref "R38") (pin "1") (pinfunction "1_1") (pintype "passive"))
      (node (ref "R39") (pin "1") (pinfunction "1_1") (pintype "passive"))
    )
    (net (code "67") (name "Net-(Q15-B)") (class "Default")
      (node (ref "C5") (pin "2") (pinfunction "2_2") (pintype "passive"))
      (node (ref "D25") (pin "C") (pinfunction "C_C") (pintype "passive"))
      (node (ref "Q15") (pin "2") (pinfunction "B_2") (pintype "passive"))
      (node (ref "R26") (pin "2") (pinfunction "2_2") (pintype "passive"))
    )
    (net (code "68") (name "Net-(Q15-C)") (class "Default")
      (node (ref "Q15") (pin "3") (pinfunction "C_3") (pintype "passive"))
      (node (ref "R40") (pin "1") (pinfunction "1_1") (pintype "passive"))
      (node (ref "R41") (pin "1") (pinfunction "1_1") (pintype "passive"))
    )
    (net (code "69") (name "Net-(Q16-B)") (class "Default")
      (node (ref "C6") (pin "2") (pinfunction "2_2") (pintype "passive"))
      (node (ref "D26") (pin "C") (pinfunction "C_C") (pintype "passive"))
      (node (ref "Q16") (pin "2") (pinfunction "B_2") (pintype "passive"))
      (node (ref "R27") (pin "2") (pinfunction "2_2") (pintype "passive"))
    )
    (net (code "70") (name "Net-(Q16-C)") (class "Default")
      (node (ref "Q16") (pin "3") (pinfunction "C_3") (pintype "passive"))
      (node (ref "R42") (pin "1") (pinfunction "1_1") (pintype "passive"))
      (node (ref "R43") (pin "1") (pinfunction "1_1") (pintype "passive"))
    )
    (net (code "71") (name "Net-(Q17-B)") (class "Default")
      (node (ref "C7") (pin "2") (pinfunction "2_2") (pintype "passive"))
      (node (ref "D27") (pin "C") (pinfunction "C_C") (pintype "passive"))
      (node (ref "Q17") (pin "2") (pinfunction "B_2") (pintype "passive"))
      (node (ref "R28") (pin "2") (pinfunction "2_2") (pintype "passive"))
    )
    (net (code "72") (name "Net-(Q17-C)") (class "Default")
      (node (ref "Q17") (pin "3") (pinfunction "C_3") (pintype "passive"))
      (node (ref "R44") (pin "1") (pinfunction "1_1") (pintype "passive"))
      (node (ref "R45") (pin "1") (pinfunction "1_1") (pintype "passive"))
    )
    (net (code "73") (name "Net-(Q18-B)") (class "Default")
      (node (ref "C8") (pin "2") (pinfunction "2_2") (pintype "passive"))
      (node (ref "D28") (pin "C") (pinfunction "C_C") (pintype "passive"))
      (node (ref "Q18") (pin "2") (pinfunction "B_2") (pintype "passive"))
      (node (ref "R29") (pin "2") (pinfunction "2_2") (pintype "passive"))
    )
    (net (code "74") (name "Net-(Q18-C)") (class "Default")
      (node (ref "Q18") (pin "3") (pinfunction "C_3") (pintype "passive"))
      (node (ref "R46") (pin "1") (pinfunction "1_1") (pintype "passive"))
      (node (ref "R47") (pin "1") (pinfunction "1_1") (pintype "passive"))
    )
    (net (code "75") (name "Net-(Q19-B)") (class "Default")
      (node (ref "C9") (pin "2") (pinfunction "2_2") (pintype "passive"))
      (node (ref "D29") (pin "C") (pinfunction "C_C") (pintype "passive"))
      (node (ref "Q19") (pin "2") (pinfunction "B_2") (pintype "passive"))
      (node (ref "R30") (pin "2") (pinfunction "2_2") (pintype "passive"))
    )
    (net (code "76") (name "Net-(Q19-C)") (class "Default")
      (node (ref "Q19") (pin "3") (pinfunction "C_3") (pintype "passive"))
      (node (ref "R48") (pin "1") (pinfunction "1_1") (pintype "passive"))
      (node (ref "R49") (pin "1") (pinfunction "1_1") (pintype "passive"))
    )
    (net (code "77") (name "Net-(Q20-B)") (class "Default")
      (node (ref "C10") (pin "2") (pinfunction "2_2") (pintype "passive"))
      (node (ref "D30") (pin "C") (pinfunction "C_C") (pintype "passive"))
      (node (ref "Q20") (pin "2") (pinfunction "B_2") (pintype "passive"))
      (node (ref "R31") (pin "2") (pinfunction "2_2") (pintype "passive"))
    )
    (net (code "78") (name "Net-(Q20-C)") (class "Default")
      (node (ref "Q20") (pin "3") (pinfunction "C_3") (pintype "passive"))
      (node (ref "R50") (pin "1") (pinfunction "1_1") (pintype "passive"))
    )
    (net (code "79") (name "Net-(Q21A-B)") (class "Default")
      (node (ref "C14") (pin "1") (pinfunction "1_1") (pintype "passive"))
      (node (ref "Q21") (pin "2") (pinfunction "B_2") (pintype "passive"))
      (node (ref "R33") (pin "2") (pinfunction "2_2") (pintype "passive"))
      (node (ref "R35") (pin "2") (pinfunction "2_2") (pintype "passive"))
      (node (ref "R37") (pin "2") (pinfunction "2_2") (pintype "passive"))
      (node (ref "R39") (pin "2") (pinfunction "2_2") (pintype "passive"))
      (node (ref "R41") (pin "2") (pinfunction "2_2") (pintype "passive"))
      (node (ref "R43") (pin "2") (pinfunction "2_2") (pintype "passive"))
      (node (ref "R45") (pin "2") (pinfunction "2_2") (pintype "passive"))
      (node (ref "R47") (pin "2") (pinfunction "2_2") (pintype "passive"))
      (node (ref "R49") (pin "2") (pinfunction "2_2") (pintype "passive"))
      (node (ref "R50") (pin "2") (pinfunction "2_2") (pintype "passive"))
      (node (ref "R60") (pin "1") (pinfunction "1_1") (pintype "passive"))
    )
    (net (code "80") (name "Net-(Q21A-C)") (class "Default")
      (node (ref "C16") (pin "1") (pinfunction "1_1") (pintype "passive"))
      (node (ref "Q21") (pin "1") (pinfunction "C_1") (pintype "passive"))
      (node (ref "Q25") (pin "2") (pinfunction "B_2") (pintype "passive"))
      (node (ref "R53") (pin "1") (pinfunction "1_1") (pintype "passive"))
    )
    (net (code "81") (name "Net-(Q21A-E)") (class "Default")
      (node (ref "Q21") (pin "3") (pinfunction "E_3") (pintype "passive"))
      (node (ref "Q21") (pin "4") (pinfunction "E_4") (pintype "passive"))
      (node (ref "R54") (pin "2") (pinfunction "2_2") (pintype "passive"))
    )
    (net (code "82") (name "Net-(Q22-B)") (class "Default")
      (node (ref "Q22") (pin "2") (pinfunction "B_2") (pintype "passive"))
      (node (ref "Q23") (pin "1") (pinfunction "E_1") (pintype "passive"))
      (node (ref "R59") (pin "1") (pinfunction "1_1") (pintype "passive"))
    )
    (net (code "83") (name "Net-(Q23-B)") (class "Default")
      (node (ref "Q23") (pin "2") (pinfunction "B_2") (pintype "passive"))
      (node (ref "Q26") (pin "6") (pinfunction "C_6") (pintype "passive"))
      (node (ref "R65") (pin "2") (pinfunction "2_2") (pintype "passive"))
    )
    (net (code "84") (name "Net-(Q25-C)") (class "Default")
      (node (ref "Q25") (pin "3") (pinfunction "C_3") (pintype "passive"))
      (node (ref "R64") (pin "1") (pinfunction "1_1") (pintype "passive"))
    )
    (net (code "85") (name "Net-(Q25-E)") (class "Default")
      (node (ref "C14") (pin "2") (pinfunction "2_2") (pintype "passive"))
      (node (ref "Q25") (pin "1") (pinfunction "E_1") (pintype "passive"))
      (node (ref "R61") (pin "2") (pinfunction "2_2") (pintype "passive"))
      (node (ref "R63") (pin "2") (pinfunction "2_2") (pintype "passive"))
    )
    (net (code "86") (name "Net-(Q26A-B)") (class "Default")
      (node (ref "D33") (pin "A") (pinfunction "A_A") (pintype "passive"))
      (node (ref "Q26") (pin "2") (pinfunction "B_2") (pintype "passive"))
      (node (ref "R67") (pin "2") (pinfunction "2_2") (pintype "passive"))
    )
    (net (code "87") (name "Net-(Q26A-E)") (class "Default")
      (node (ref "Q26") (pin "3") (pinfunction "E_3") (pintype "passive"))
      (node (ref "Q26") (pin "4") (pinfunction "E_4") (pintype "passive"))
      (node (ref "R66") (pin "1") (pinfunction "1_1") (pintype "passive"))
    )
    (net (code "88") (name "Net-(Q26B-B)") (class "Default")
      (node (ref "Q26") (pin "5") (pinfunction "B_5") (pintype "passive"))
      (node (ref "R56") (pin "2") (pinfunction "2_2") (pintype "passive"))
      (node (ref "R57") (pin "1") (pinfunction "1_1") (pintype "passive"))
    )
    (net (code "89") (name "VCC") (class "Default")
      (node (ref "C15") (pin "+") (pinfunction "+_+") (pintype "passive"))
      (node (ref "Q21") (pin "6") (pinfunction "C_6") (pintype "passive"))
      (node (ref "R53") (pin "2") (pinfunction "2_2") (pintype "passive"))
      (node (ref "R64") (pin "2") (pinfunction "2_2") (pintype "passive"))
      (node (ref "U$2") (pin "AA2") (pinfunction "1_AA2") (pintype "bidirectional"))
    )
    (net (code "90") (name "unconnected-(E1A-PRE-Pad4)") (class "Default")
      (node (ref "E1") (pin "4") (pinfunction "PRE_4") (pintype "input"))
    )
    (net (code "91") (name "unconnected-(E1A-Q-Pad5)") (class "Default")
      (node (ref "E1") (pin "5") (pinfunction "Q_5") (pintype "output"))
    )
    (net (code "92") (name "unconnected-(E1B-PRE-Pad10)") (class "Default")
      (node (ref "E1") (pin "10") (pinfunction "PRE_10") (pintype "input"))
    )
    (net (code "93") (name "unconnected-(E1B-Q-Pad9)") (class "Default")
      (node (ref "E1") (pin "9") (pinfunction "Q_9") (pintype "output"))
    )
    (net (code "94") (name "unconnected-(E2A-PRE-Pad4)") (class "Default")
      (node (ref "E2") (pin "4") (pinfunction "PRE_4") (pintype "input"))
    )
    (net (code "95") (name "unconnected-(E2A-Q-Pad5)") (class "Default")
      (node (ref "E2") (pin "5") (pinfunction "Q_5") (pintype "output"))
    )
    (net (code "96") (name "unconnected-(E2B-PRE-Pad10)") (class "Default")
      (node (ref "E2") (pin "10") (pinfunction "PRE_10") (pintype "input"))
    )
    (net (code "97") (name "unconnected-(E2B-Q-Pad9)") (class "Default")
      (node (ref "E2") (pin "9") (pinfunction "Q_9") (pintype "output"))
    )
    (net (code "98") (name "unconnected-(E3A-PRE-Pad4)") (class "Default")
      (node (ref "E3") (pin "4") (pinfunction "PRE_4") (pintype "input"))
    )
    (net (code "99") (name "unconnected-(E3A-Q-Pad5)") (class "Default")
      (node (ref "E3") (pin "5") (pinfunction "Q_5") (pintype "output"))
    )
    (net (code "100") (name "unconnected-(E3B-PRE-Pad10)") (class "Default")
      (node (ref "E3") (pin "10") (pinfunction "PRE_10") (pintype "input"))
    )
    (net (code "101") (name "unconnected-(E3B-Q-Pad9)") (class "Default")
      (node (ref "E3") (pin "9") (pinfunction "Q_9") (pintype "output"))
    )
    (net (code "102") (name "unconnected-(E4A-PRE-Pad4)") (class "Default")
      (node (ref "E4") (pin "4") (pinfunction "PRE_4") (pintype "input"))
    )
    (net (code "103") (name "unconnected-(E4A-Q-Pad5)") (class "Default")
      (node (ref "E4") (pin "5") (pinfunction "Q_5") (pintype "output"))
    )
    (net (code "104") (name "unconnected-(E4B-PRE-Pad10)") (class "Default")
      (node (ref "E4") (pin "10") (pinfunction "PRE_10") (pintype "input"))
    )
    (net (code "105") (name "unconnected-(E4B-Q-Pad9)") (class "Default")
      (node (ref "E4") (pin "9") (pinfunction "Q_9") (pintype "output"))
    )
    (net (code "106") (name "unconnected-(E5A-PRE-Pad4)") (class "Default")
      (node (ref "E5") (pin "4") (pinfunction "PRE_4") (pintype "input"))
    )
    (net (code "107") (name "unconnected-(E5A-Q-Pad5)") (class "Default")
      (node (ref "E5") (pin "5") (pinfunction "Q_5") (pintype "output"))
    )
    (net (code "108") (name "unconnected-(E5B-PRE-Pad10)") (class "Default")
      (node (ref "E5") (pin "10") (pinfunction "PRE_10") (pintype "input"))
    )
    (net (code "109") (name "unconnected-(E5B-Q-Pad9)") (class "Default")
      (node (ref "E5") (pin "9") (pinfunction "Q_9") (pintype "output"))
    )
  )
)
